# ESL.net
KiCad netlist of a schematic drawn in Altium Designer
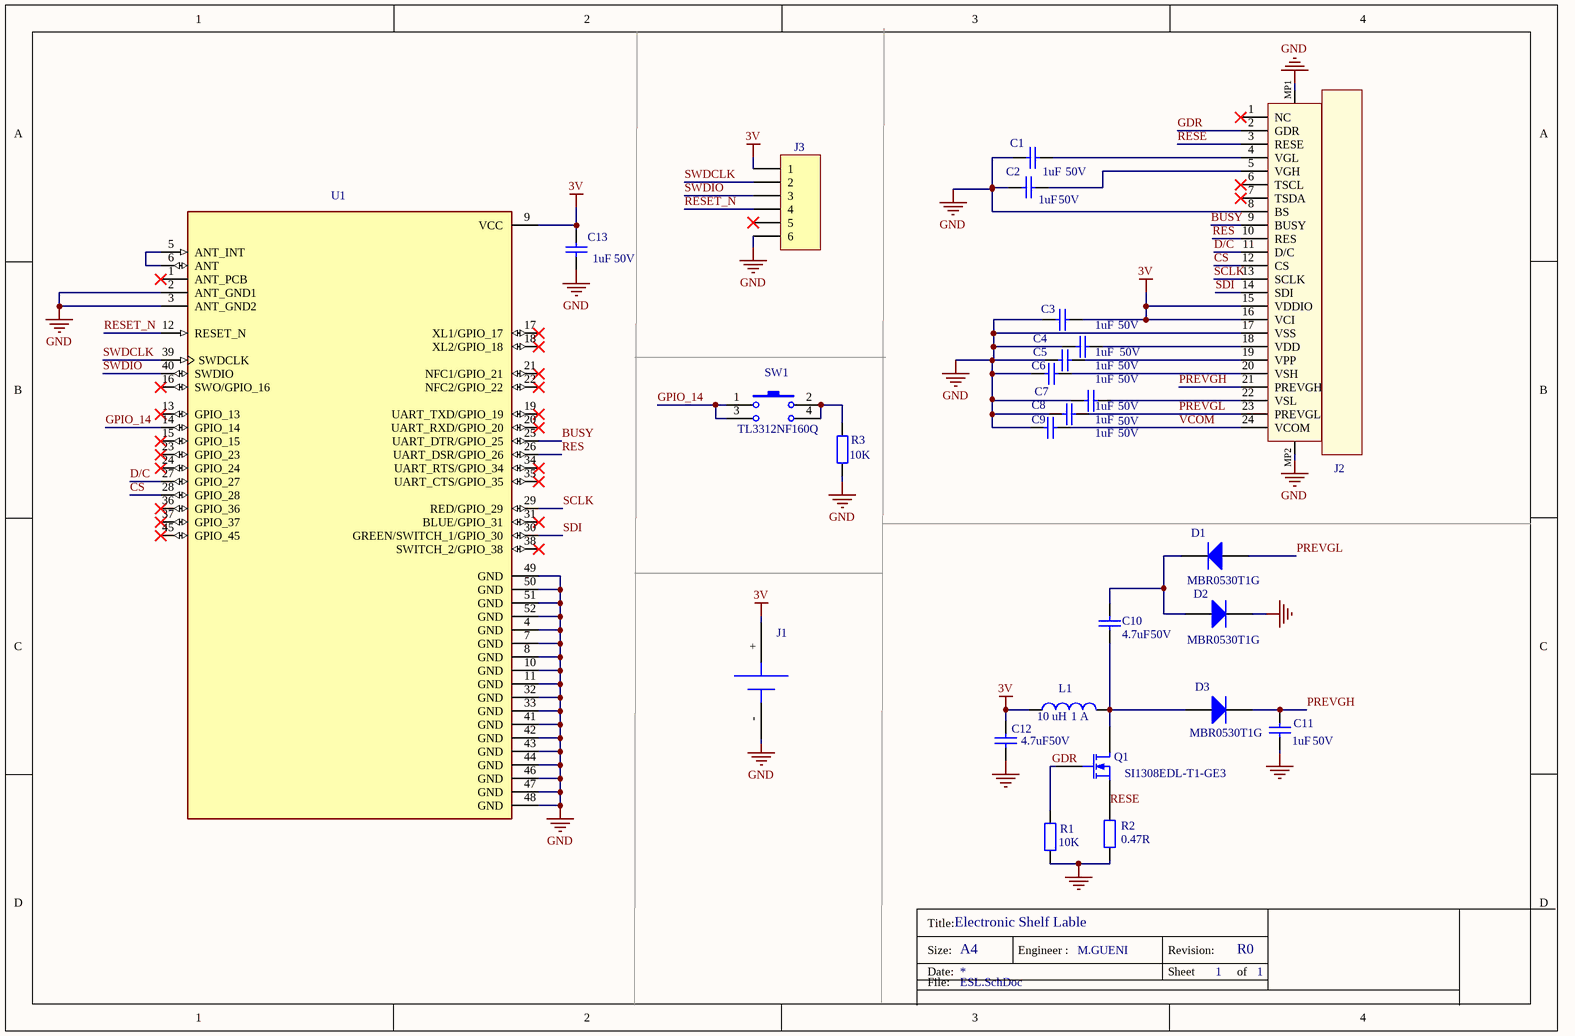
[diagram p0: ESL.SchDoc]

(export (version "E")
  (design (tool "Eeschema 10.0.6"))
  (components
    (comp (ref "C1")
      (value "Capacitor")
      (footprint "CAPC1608N")
      (fields
        (field (name "PART NUMBER") "CAP-000000001")
        (field (name "VALUE 1") "1uF")
        (field (name "VALUE 2") "50V")
      )
      (libsource (lib "Datab") (part "Capacitor"))
    )
    (comp (ref "C2")
      (value "Capacitor")
      (footprint "CAPC1608N")
      (fields
        (field (name "PART NUMBER") "CAP-000000001")
        (field (name "VALUE 1") "1uF")
        (field (name "VALUE 2") "50V")
      )
      (libsource (lib "Datab") (part "Capacitor"))
    )
    (comp (ref "C3")
      (value "Capacitor")
      (footprint "CAPC1608N")
      (fields
        (field (name "PART NUMBER") "CAP-000000001")
        (field (name "VALUE 1") "1uF")
        (field (name "VALUE 2") "50V")
      )
      (libsource (lib "Datab") (part "Capacitor"))
    )
    (comp (ref "C4")
      (value "Capacitor")
      (footprint "CAPC1608N")
      (fields
        (field (name "PART NUMBER") "CAP-000000001")
        (field (name "VALUE 1") "1uF")
        (field (name "VALUE 2") "50V")
      )
      (libsource (lib "Datab") (part "Capacitor"))
    )
    (comp (ref "C5")
      (value "Capacitor")
      (footprint "CAPC1608N")
      (fields
        (field (name "PART NUMBER") "CAP-000000001")
        (field (name "VALUE 1") "1uF")
        (field (name "VALUE 2") "50V")
      )
      (libsource (lib "Datab") (part "Capacitor"))
    )
    (comp (ref "C6")
      (value "Capacitor")
      (footprint "CAPC1608N")
      (fields
        (field (name "PART NUMBER") "CAP-000000001")
        (field (name "VALUE 1") "1uF")
        (field (name "VALUE 2") "50V")
      )
      (libsource (lib "Datab") (part "Capacitor"))
    )
    (comp (ref "C7")
      (value "Capacitor")
      (footprint "CAPC1608N")
      (fields
        (field (name "PART NUMBER") "CAP-000000001")
        (field (name "VALUE 1") "1uF")
        (field (name "VALUE 2") "50V")
      )
      (libsource (lib "Datab") (part "Capacitor"))
    )
    (comp (ref "C8")
      (value "Capacitor")
      (footprint "CAPC1608N")
      (fields
        (field (name "PART NUMBER") "CAP-000000001")
        (field (name "VALUE 1") "1uF")
        (field (name "VALUE 2") "50V")
      )
      (libsource (lib "Datab") (part "Capacitor"))
    )
    (comp (ref "C9")
      (value "Capacitor")
      (footprint "CAPC1608N")
      (fields
        (field (name "PART NUMBER") "CAP-000000001")
        (field (name "VALUE 1") "1uF")
        (field (name "VALUE 2") "50V")
      )
      (libsource (lib "Datab") (part "Capacitor"))
    )
    (comp (ref "C10")
      (value "Capacitor")
      (footprint "CAPC2012N")
      (fields
        (field (name "PART NUMBER") "CAP-000000002")
        (field (name "VALUE 1") "4.7uF")
        (field (name "VALUE 2") "50V")
      )
      (libsource (lib "Datab") (part "Capacitor"))
    )
    (comp (ref "C11")
      (value "Capacitor")
      (footprint "CAPC1608N")
      (fields
        (field (name "PART NUMBER") "CAP-000000001")
        (field (name "VALUE 1") "1uF")
        (field (name "VALUE 2") "50V")
      )
      (libsource (lib "Datab") (part "Capacitor"))
    )
    (comp (ref "C12")
      (value "Capacitor")
      (footprint "CAPC2012N")
      (fields
        (field (name "PART NUMBER") "CAP-000000002")
        (field (name "VALUE 1") "4.7uF")
        (field (name "VALUE 2") "50V")
      )
      (libsource (lib "Datab") (part "Capacitor"))
    )
    (comp (ref "C13")
      (value "Capacitor")
      (footprint "CAPC1608N")
      (fields
        (field (name "PART NUMBER") "CAP-000000001")
        (field (name "VALUE 1") "1uF")
        (field (name "VALUE 2") "50V")
      )
      (libsource (lib "Datab") (part "Capacitor"))
    )
    (comp (ref "D1")
      (value "MBR0530T1G")
      (footprint "DO-SOD-123")
      (description "Diode")
      (fields (field (name "PART NUMBER") "DIR-000000001"))
      (libsource (lib "Datab") (part "Diode"))
    )
    (comp (ref "D2")
      (value "MBR0530T1G")
      (footprint "DO-SOD-123")
      (description "Diode")
      (fields (field (name "PART NUMBER") "DIR-000000001"))
      (libsource (lib "Datab") (part "Diode"))
    )
    (comp (ref "D3")
      (value "MBR0530T1G")
      (footprint "DO-SOD-123")
      (description "Diode")
      (fields (field (name "PART NUMBER") "DIR-000000001"))
      (libsource (lib "Datab") (part "Diode"))
    )
    (comp (ref "J1")
      (value "Battery_Holder")
      (footprint "Battery_Holder")
      (fields (field (name "PART NUMBER") "CON-000000002"))
      (libsource (lib "Datab") (part "Battery_Holder"))
    )
    (comp (ref "J2")
      (value "WR-FPC")
      (footprint "WR-FPC-68712414022")
      (fields (field (name "PART NUMBER") "CON-000000001"))
      (libsource (lib "Datab") (part "WR-FPC"))
    )
    (comp (ref "J3")
      (value "282834-6")
      (footprint "282834-6")
      (description "Header, 6-Pin")
      (fields (field (name "PART NUMBER") "CON-000000003"))
      (libsource (lib "Datab") (part "Header 6"))
    )
    (comp (ref "L1")
      (value "1239AS-H-100M=P2")
      (footprint "IND_2520")
      (description "Inductor")
      (fields
        (field (name "PART NUMBER") "IND-000000001")
        (field (name "VALUE 1") "10 uH")
        (field (name "VALUE 2") "1 A")
      )
      (libsource (lib "Datab") (part "Inductor"))
    )
    (comp (ref "Q1")
      (value "SI1308EDL-T1-GE3")
      (footprint "MOS-SOT-323-3")
      (fields (field (name "PART NUMBER") "TRM-000000001"))
      (libsource (lib "Datab") (part "SI1308EDL-T1-GE3"))
    )
    (comp (ref "R1")
      (value "Resistor")
      (footprint "RESC1608N")
      (fields (field (name "PART NUMBER") "RES-000000002") (field (name "VALUE 1") "10K"))
      (libsource (lib "Datab") (part "Resistor"))
    )
    (comp (ref "R2")
      (value "Resistor")
      (footprint "RESC1608N")
      (fields (field (name "PART NUMBER") "RES-000000001") (field (name "VALUE 1") "0.47R"))
      (libsource (lib "Datab") (part "Resistor"))
    )
    (comp (ref "R3")
      (value "Resistor")
      (footprint "RESC1608N")
      (fields (field (name "PART NUMBER") "RES-000000002") (field (name "VALUE 1") "10K"))
      (libsource (lib "Datab") (part "Resistor"))
    )
    (comp (ref "SW1")
      (value "TL3312NF160Q")
      (footprint "SPST-TL3312NF160Q")
      (fields (field (name "PART NUMBER") "SWC-000000001"))
      (libsource (lib "Datab") (part "TL3312NF160Q"))
    )
    (comp (ref "U1")
      (value "ANNA-B112-01B")
      (footprint "ANNA-B112-01B")
      (fields
        (field (name "PART NUMBER") "RFC-000000001")
        (field (name "MF") "U-Blox America")
        (field (name "MP") "ANNA-B112")
      )
      (libsource (lib "Datab") (part "ANNA-B112-01B"))
    )
  )
  (nets
    (net (code "1") (name "/BUSY") (class "Default")
      (node (ref "J2") (pin "9") (pinfunction "BUSY_9") (pintype "passive"))
      (node (ref "U1") (pin "25") (pinfunction "UART_DTR/GPIO_25_25") (pintype "bidirectional"))
    )
    (net (code "2") (name "/CS") (class "Default")
      (node (ref "J2") (pin "12") (pinfunction "CS_12") (pintype "passive"))
      (node (ref "U1") (pin "28") (pinfunction "GPIO_28_28") (pintype "bidirectional"))
    )
    (net (code "3") (name "/D{slash}C") (class "Default")
      (node (ref "J2") (pin "11") (pinfunction "D/C_11") (pintype "passive"))
      (node (ref "U1") (pin "27") (pinfunction "GPIO_27_27") (pintype "bidirectional"))
    )
    (net (code "4") (name "/GDR") (class "Default")
      (node (ref "J2") (pin "2") (pinfunction "GDR_2") (pintype "passive"))
      (node (ref "Q1") (pin "1") (pinfunction "G_1") (pintype "passive"))
      (node (ref "R1") (pin "2") (pinfunction "2_2") (pintype "passive"))
    )
    (net (code "5") (name "/GPIO_14") (class "Default")
      (node (ref "SW1") (pin "1") (pinfunction "1_1") (pintype "passive"))
      (node (ref "SW1") (pin "3") (pinfunction "3_3") (pintype "passive"))
      (node (ref "U1") (pin "14") (pinfunction "GPIO_14_14") (pintype "bidirectional"))
    )
    (net (code "6") (name "/PREVGH") (class "Default")
      (node (ref "C11") (pin "2") (pinfunction "2_2") (pintype "passive"))
      (node (ref "D3") (pin "2") (pinfunction "K_2") (pintype "passive"))
      (node (ref "J2") (pin "21") (pinfunction "PREVGH_21") (pintype "passive"))
    )
    (net (code "7") (name "/PREVGL") (class "Default")
      (node (ref "C8") (pin "2") (pinfunction "2_2") (pintype "passive"))
      (node (ref "D1") (pin "1") (pinfunction "A_1") (pintype "passive"))
      (node (ref "J2") (pin "23") (pinfunction "PREVGL_23") (pintype "passive"))
    )
    (net (code "8") (name "/RES") (class "Default")
      (node (ref "J2") (pin "10") (pinfunction "RES_10") (pintype "passive"))
      (node (ref "U1") (pin "26") (pinfunction "UART_DSR/GPIO_26_26") (pintype "bidirectional"))
    )
    (net (code "9") (name "/RESE") (class "Default")
      (node (ref "J2") (pin "3") (pinfunction "RESE_3") (pintype "passive"))
      (node (ref "Q1") (pin "2") (pinfunction "S_2") (pintype "passive"))
      (node (ref "R2") (pin "2") (pinfunction "2_2") (pintype "passive"))
    )
    (net (code "10") (name "/RESET_N") (class "Default")
      (node (ref "J3") (pin "4") (pinfunction "4_4") (pintype "passive"))
      (node (ref "U1") (pin "12") (pinfunction "RESET_N_12") (pintype "input"))
    )
    (net (code "11") (name "/SCLK") (class "Default")
      (node (ref "J2") (pin "13") (pinfunction "SCLK_13") (pintype "passive"))
      (node (ref "U1") (pin "29") (pinfunction "RED/GPIO_29_29") (pintype "bidirectional"))
    )
    (net (code "12") (name "/SDI") (class "Default")
      (node (ref "J2") (pin "14") (pinfunction "SDI_14") (pintype "passive"))
      (node (ref "U1") (pin "30") (pinfunction "GREEN/SWITCH_1/GPIO_30_30") (pintype "bidirectional"))
    )
    (net (code "13") (name "/SWDCLK") (class "Default")
      (node (ref "J3") (pin "2") (pinfunction "2_2") (pintype "passive"))
      (node (ref "U1") (pin "39") (pinfunction "SWDCLK_39") (pintype "input"))
    )
    (net (code "14") (name "/SWDIO") (class "Default")
      (node (ref "J3") (pin "3") (pinfunction "3_3") (pintype "passive"))
      (node (ref "U1") (pin "40") (pinfunction "SWDIO_40") (pintype "bidirectional"))
    )
    (net (code "15") (name "/VCOM") (class "Default")
      (node (ref "C9") (pin "2") (pinfunction "2_2") (pintype "passive"))
      (node (ref "J2") (pin "24") (pinfunction "VCOM_24") (pintype "passive"))
    )
    (net (code "16") (name "3V") (class "Default")
      (node (ref "C12") (pin "2") (pinfunction "2_2") (pintype "passive"))
      (node (ref "C13") (pin "2") (pinfunction "2_2") (pintype "passive"))
      (node (ref "C3") (pin "2") (pinfunction "2_2") (pintype "passive"))
      (node (ref "J1") (pin "+") (pinfunction "+_+") (pintype "passive"))
      (node (ref "J2") (pin "15") (pinfunction "VDDIO_15") (pintype "passive"))
      (node (ref "J2") (pin "16") (pinfunction "VCI_16") (pintype "passive"))
      (node (ref "J3") (pin "1") (pinfunction "1_1") (pintype "passive"))
      (node (ref "L1") (pin "1") (pinfunction "1_1") (pintype "passive"))
      (node (ref "U1") (pin "9") (pinfunction "VCC_9") (pintype "power_in"))
    )
    (net (code "17") (name "GND") (class "Default")
      (node (ref "C1") (pin "1") (pinfunction "1_1") (pintype "passive"))
      (node (ref "C11") (pin "1") (pinfunction "1_1") (pintype "passive"))
      (node (ref "C12") (pin "1") (pinfunction "1_1") (pintype "passive"))
      (node (ref "C13") (pin "1") (pinfunction "1_1") (pintype "passive"))
      (node (ref "C2") (pin "2") (pinfunction "2_2") (pintype "passive"))
      (node (ref "C3") (pin "1") (pinfunction "1_1") (pintype "passive"))
      (node (ref "C4") (pin "1") (pinfunction "1_1") (pintype "passive"))
      (node (ref "C5") (pin "1") (pinfunction "1_1") (pintype "passive"))
      (node (ref "C6") (pin "1") (pinfunction "1_1") (pintype "passive"))
      (node (ref "C7") (pin "1") (pinfunction "1_1") (pintype "passive"))
      (node (ref "C8") (pin "1") (pinfunction "1_1") (pintype "passive"))
      (node (ref "C9") (pin "1") (pinfunction "1_1") (pintype "passive"))
      (node (ref "D2") (pin "2") (pinfunction "K_2") (pintype "passive"))
      (node (ref "J1") (pin "-") (pinfunction "-_-") (pintype "passive"))
      (node (ref "J2") (pin "17") (pinfunction "VSS_17") (pintype "passive"))
      (node (ref "J2") (pin "8") (pinfunction "BS_8") (pintype "passive"))
      (node (ref "J2") (pin "MP1") (pinfunction "MP1_MP1") (pintype "passive"))
      (node (ref "J2") (pin "MP2") (pinfunction "MP2_MP2") (pintype "passive"))
      (node (ref "J3") (pin "6") (pinfunction "6_6") (pintype "passive"))
      (node (ref "R1") (pin "1") (pinfunction "1_1") (pintype "passive"))
      (node (ref "R2") (pin "1") (pinfunction "1_1") (pintype "passive"))
      (node (ref "R3") (pin "1") (pinfunction "1_1") (pintype "passive"))
      (node (ref "U1") (pin "10") (pinfunction "GND_10") (pintype "power_in"))
      (node (ref "U1") (pin "11") (pinfunction "GND_11") (pintype "power_in"))
      (node (ref "U1") (pin "2") (pinfunction "ANT_GND1_2") (pintype "power_in"))
      (node (ref "U1") (pin "3") (pinfunction "ANT_GND2_3") (pintype "power_in"))
      (node (ref "U1") (pin "32") (pinfunction "GND_32") (pintype "power_in"))
      (node (ref "U1") (pin "33") (pinfunction "GND_33") (pintype "power_in"))
      (node (ref "U1") (pin "4") (pinfunction "GND_4") (pintype "power_in"))
      (node (ref "U1") (pin "41") (pinfunction "GND_41") (pintype "power_in"))
      (node (ref "U1") (pin "42") (pinfunction "GND_42") (pintype "power_in"))
      (node (ref "U1") (pin "43") (pinfunction "GND_43") (pintype "power_in"))
      (node (ref "U1") (pin "44") (pinfunction "GND_44") (pintype "power_in"))
      (node (ref "U1") (pin "46") (pinfunction "GND_46") (pintype "power_in"))
      (node (ref "U1") (pin "47") (pinfunction "GND_47") (pintype "power_in"))
      (node (ref "U1") (pin "48") (pinfunction "GND_48") (pintype "power_in"))
      (node (ref "U1") (pin "49") (pinfunction "GND_49") (pintype "power_in"))
      (node (ref "U1") (pin "50") (pinfunction "GND_50") (pintype "power_in"))
      (node (ref "U1") (pin "51") (pinfunction "GND_51") (pintype "power_in"))
      (node (ref "U1") (pin "52") (pinfunction "GND_52") (pintype "power_in"))
      (node (ref "U1") (pin "7") (pinfunction "GND_7") (pintype "power_in"))
      (node (ref "U1") (pin "8") (pinfunction "GND_8") (pintype "power_in"))
    )
    (net (code "18") (name "Net-(D1-K)") (class "Default")
      (node (ref "C10") (pin "2") (pinfunction "2_2") (pintype "passive"))
      (node (ref "D1") (pin "2") (pinfunction "K_2") (pintype "passive"))
      (node (ref "D2") (pin "1") (pinfunction "A_1") (pintype "passive"))
    )
    (net (code "19") (name "Net-(D3-A)") (class "Default")
      (node (ref "C10") (pin "1") (pinfunction "1_1") (pintype "passive"))
      (node (ref "D3") (pin "1") (pinfunction "A_1") (pintype "passive"))
      (node (ref "L1") (pin "2") (pinfunction "2_2") (pintype "passive"))
      (node (ref "Q1") (pin "3") (pinfunction "D_3") (pintype "passive"))
    )
    (net (code "20") (name "Net-(J2-VDD)") (class "Default")
      (node (ref "C4") (pin "2") (pinfunction "2_2") (pintype "passive"))
      (node (ref "J2") (pin "18") (pinfunction "VDD_18") (pintype "passive"))
    )
    (net (code "21") (name "Net-(J2-VGH)") (class "Default")
      (node (ref "C2") (pin "1") (pinfunction "1_1") (pintype "passive"))
      (node (ref "J2") (pin "5") (pinfunction "VGH_5") (pintype "passive"))
    )
    (net (code "22") (name "Net-(J2-VGL)") (class "Default")
      (node (ref "C1") (pin "2") (pinfunction "2_2") (pintype "passive"))
      (node (ref "J2") (pin "4") (pinfunction "VGL_4") (pintype "passive"))
    )
    (net (code "23") (name "Net-(J2-VPP)") (class "Default")
      (node (ref "C5") (pin "2") (pinfunction "2_2") (pintype "passive"))
      (node (ref "J2") (pin "19") (pinfunction "VPP_19") (pintype "passive"))
    )
    (net (code "24") (name "Net-(J2-VSH)") (class "Default")
      (node (ref "C6") (pin "2") (pinfunction "2_2") (pintype "passive"))
      (node (ref "J2") (pin "20") (pinfunction "VSH_20") (pintype "passive"))
    )
    (net (code "25") (name "Net-(J2-VSL)") (class "Default")
      (node (ref "C7") (pin "2") (pinfunction "2_2") (pintype "passive"))
      (node (ref "J2") (pin "22") (pinfunction "VSL_22") (pintype "passive"))
    )
    (net (code "26") (name "Net-(R3-Pad2)") (class "Default")
      (node (ref "R3") (pin "2") (pinfunction "2_2") (pintype "passive"))
      (node (ref "SW1") (pin "2") (pinfunction "2_2") (pintype "passive"))
      (node (ref "SW1") (pin "4") (pinfunction "4_4") (pintype "passive"))
    )
    (net (code "27") (name "Net-(U1-ANT)") (class "Default")
      (node (ref "U1") (pin "5") (pinfunction "ANT_INT_5") (pintype "input"))
      (node (ref "U1") (pin "6") (pinfunction "ANT_6") (pintype "bidirectional"))
    )
    (net (code "28") (name "unconnected-(J2-NC-Pad1)") (class "Default")
      (node (ref "J2") (pin "1") (pinfunction "NC_1") (pintype "passive+no_connect"))
    )
    (net (code "29") (name "unconnected-(J2-TSCL-Pad6)") (class "Default")
      (node (ref "J2") (pin "6") (pinfunction "TSCL_6") (pintype "passive+no_connect"))
    )
    (net (code "30") (name "unconnected-(J2-TSDA-Pad7)") (class "Default")
      (node (ref "J2") (pin "7") (pinfunction "TSDA_7") (pintype "passive+no_connect"))
    )
    (net (code "31") (name "unconnected-(J3-Pad5)") (class "Default")
      (node (ref "J3") (pin "5") (pinfunction "5_5") (pintype "passive+no_connect"))
    )
    (net (code "32") (name "unconnected-(U1-ANT_PCB-Pad1)") (class "Default")
      (node (ref "U1") (pin "1") (pinfunction "ANT_PCB_1") (pintype "power_in+no_connect"))
    )
    (net (code "33") (name "unconnected-(U1-BLUE{slash}GPIO_31-Pad31)") (class "Default")
      (node (ref "U1") (pin "31") (pinfunction "BLUE/GPIO_31_31") (pintype "bidirectional+no_connect"))
    )
    (net (code "34") (name "unconnected-(U1-GPIO_13-Pad13)") (class "Default")
      (node (ref "U1") (pin "13") (pinfunction "GPIO_13_13") (pintype "bidirectional+no_connect"))
    )
    (net (code "35") (name "unconnected-(U1-GPIO_15-Pad15)") (class "Default")
      (node (ref "U1") (pin "15") (pinfunction "GPIO_15_15") (pintype "bidirectional+no_connect"))
    )
    (net (code "36") (name "unconnected-(U1-GPIO_23-Pad23)") (class "Default")
      (node (ref "U1") (pin "23") (pinfunction "GPIO_23_23") (pintype "bidirectional+no_connect"))
    )
    (net (code "37") (name "unconnected-(U1-GPIO_24-Pad24)") (class "Default")
      (node (ref "U1") (pin "24") (pinfunction "GPIO_24_24") (pintype "bidirectional+no_connect"))
    )
    (net (code "38") (name "unconnected-(U1-GPIO_36-Pad36)") (class "Default")
      (node (ref "U1") (pin "36") (pinfunction "GPIO_36_36") (pintype "bidirectional+no_connect"))
    )
    (net (code "39") (name "unconnected-(U1-GPIO_37-Pad37)") (class "Default")
      (node (ref "U1") (pin "37") (pinfunction "GPIO_37_37") (pintype "bidirectional+no_connect"))
    )
    (net (code "40") (name "unconnected-(U1-GPIO_45-Pad45)") (class "Default")
      (node (ref "U1") (pin "45") (pinfunction "GPIO_45_45") (pintype "bidirectional+no_connect"))
    )
    (net (code "41") (name "unconnected-(U1-NFC1{slash}GPIO_21-Pad21)") (class "Default")
      (node (ref "U1") (pin "21") (pinfunction "NFC1/GPIO_21_21") (pintype "bidirectional+no_connect"))
    )
    (net (code "42") (name "unconnected-(U1-NFC2{slash}GPIO_22-Pad22)") (class "Default")
      (node (ref "U1") (pin "22") (pinfunction "NFC2/GPIO_22_22") (pintype "bidirectional+no_connect"))
    )
    (net (code "43") (name "unconnected-(U1-SWITCH_2{slash}GPIO_38-Pad38)") (class "Default")
      (node (ref "U1") (pin "38") (pinfunction "SWITCH_2/GPIO_38_38") (pintype "bidirectional+no_connect"))
    )
    (net (code "44") (name "unconnected-(U1-SWO{slash}GPIO_16-Pad16)") (class "Default")
      (node (ref "U1") (pin "16") (pinfunction "SWO/GPIO_16_16") (pintype "bidirectional+no_connect"))
    )
    (net (code "45") (name "unconnected-(U1-UART_CTS{slash}GPIO_35-Pad35)") (class "Default")
      (node (ref "U1") (pin "35") (pinfunction "UART_CTS/GPIO_35_35") (pintype "bidirectional+no_connect"))
    )
    (net (code "46") (name "unconnected-(U1-UART_RTS{slash}GPIO_34-Pad34)") (class "Default")
      (node (ref "U1") (pin "34") (pinfunction "UART_RTS/GPIO_34_34") (pintype "bidirectional+no_connect"))
    )
    (net (code "47") (name "unconnected-(U1-UART_RXD{slash}GPIO_20-Pad20)") (class "Default")
      (node (ref "U1") (pin "20") (pinfunction "UART_RXD/GPIO_20_20") (pintype "bidirectional+no_connect"))
    )
    (net (code "48") (name "unconnected-(U1-UART_TXD{slash}GPIO_19-Pad19)") (class "Default")
      (node (ref "U1") (pin "19") (pinfunction "UART_TXD/GPIO_19_19") (pintype "bidirectional+no_connect"))
    )
    (net (code "49") (name "unconnected-(U1-XL1{slash}GPIO_17-Pad17)") (class "Default")
      (node (ref "U1") (pin "17") (pinfunction "XL1/GPIO_17_17") (pintype "bidirectional+no_connect"))
    )
    (net (code "50") (name "unconnected-(U1-XL2{slash}GPIO_18-Pad18)") (class "Default")
      (node (ref "U1") (pin "18") (pinfunction "XL2/GPIO_18_18") (pintype "bidirectional+no_connect"))
    )
  )
)
